# eMMC_SD.net
KiCad netlist of a schematic drawn in Altium Designer
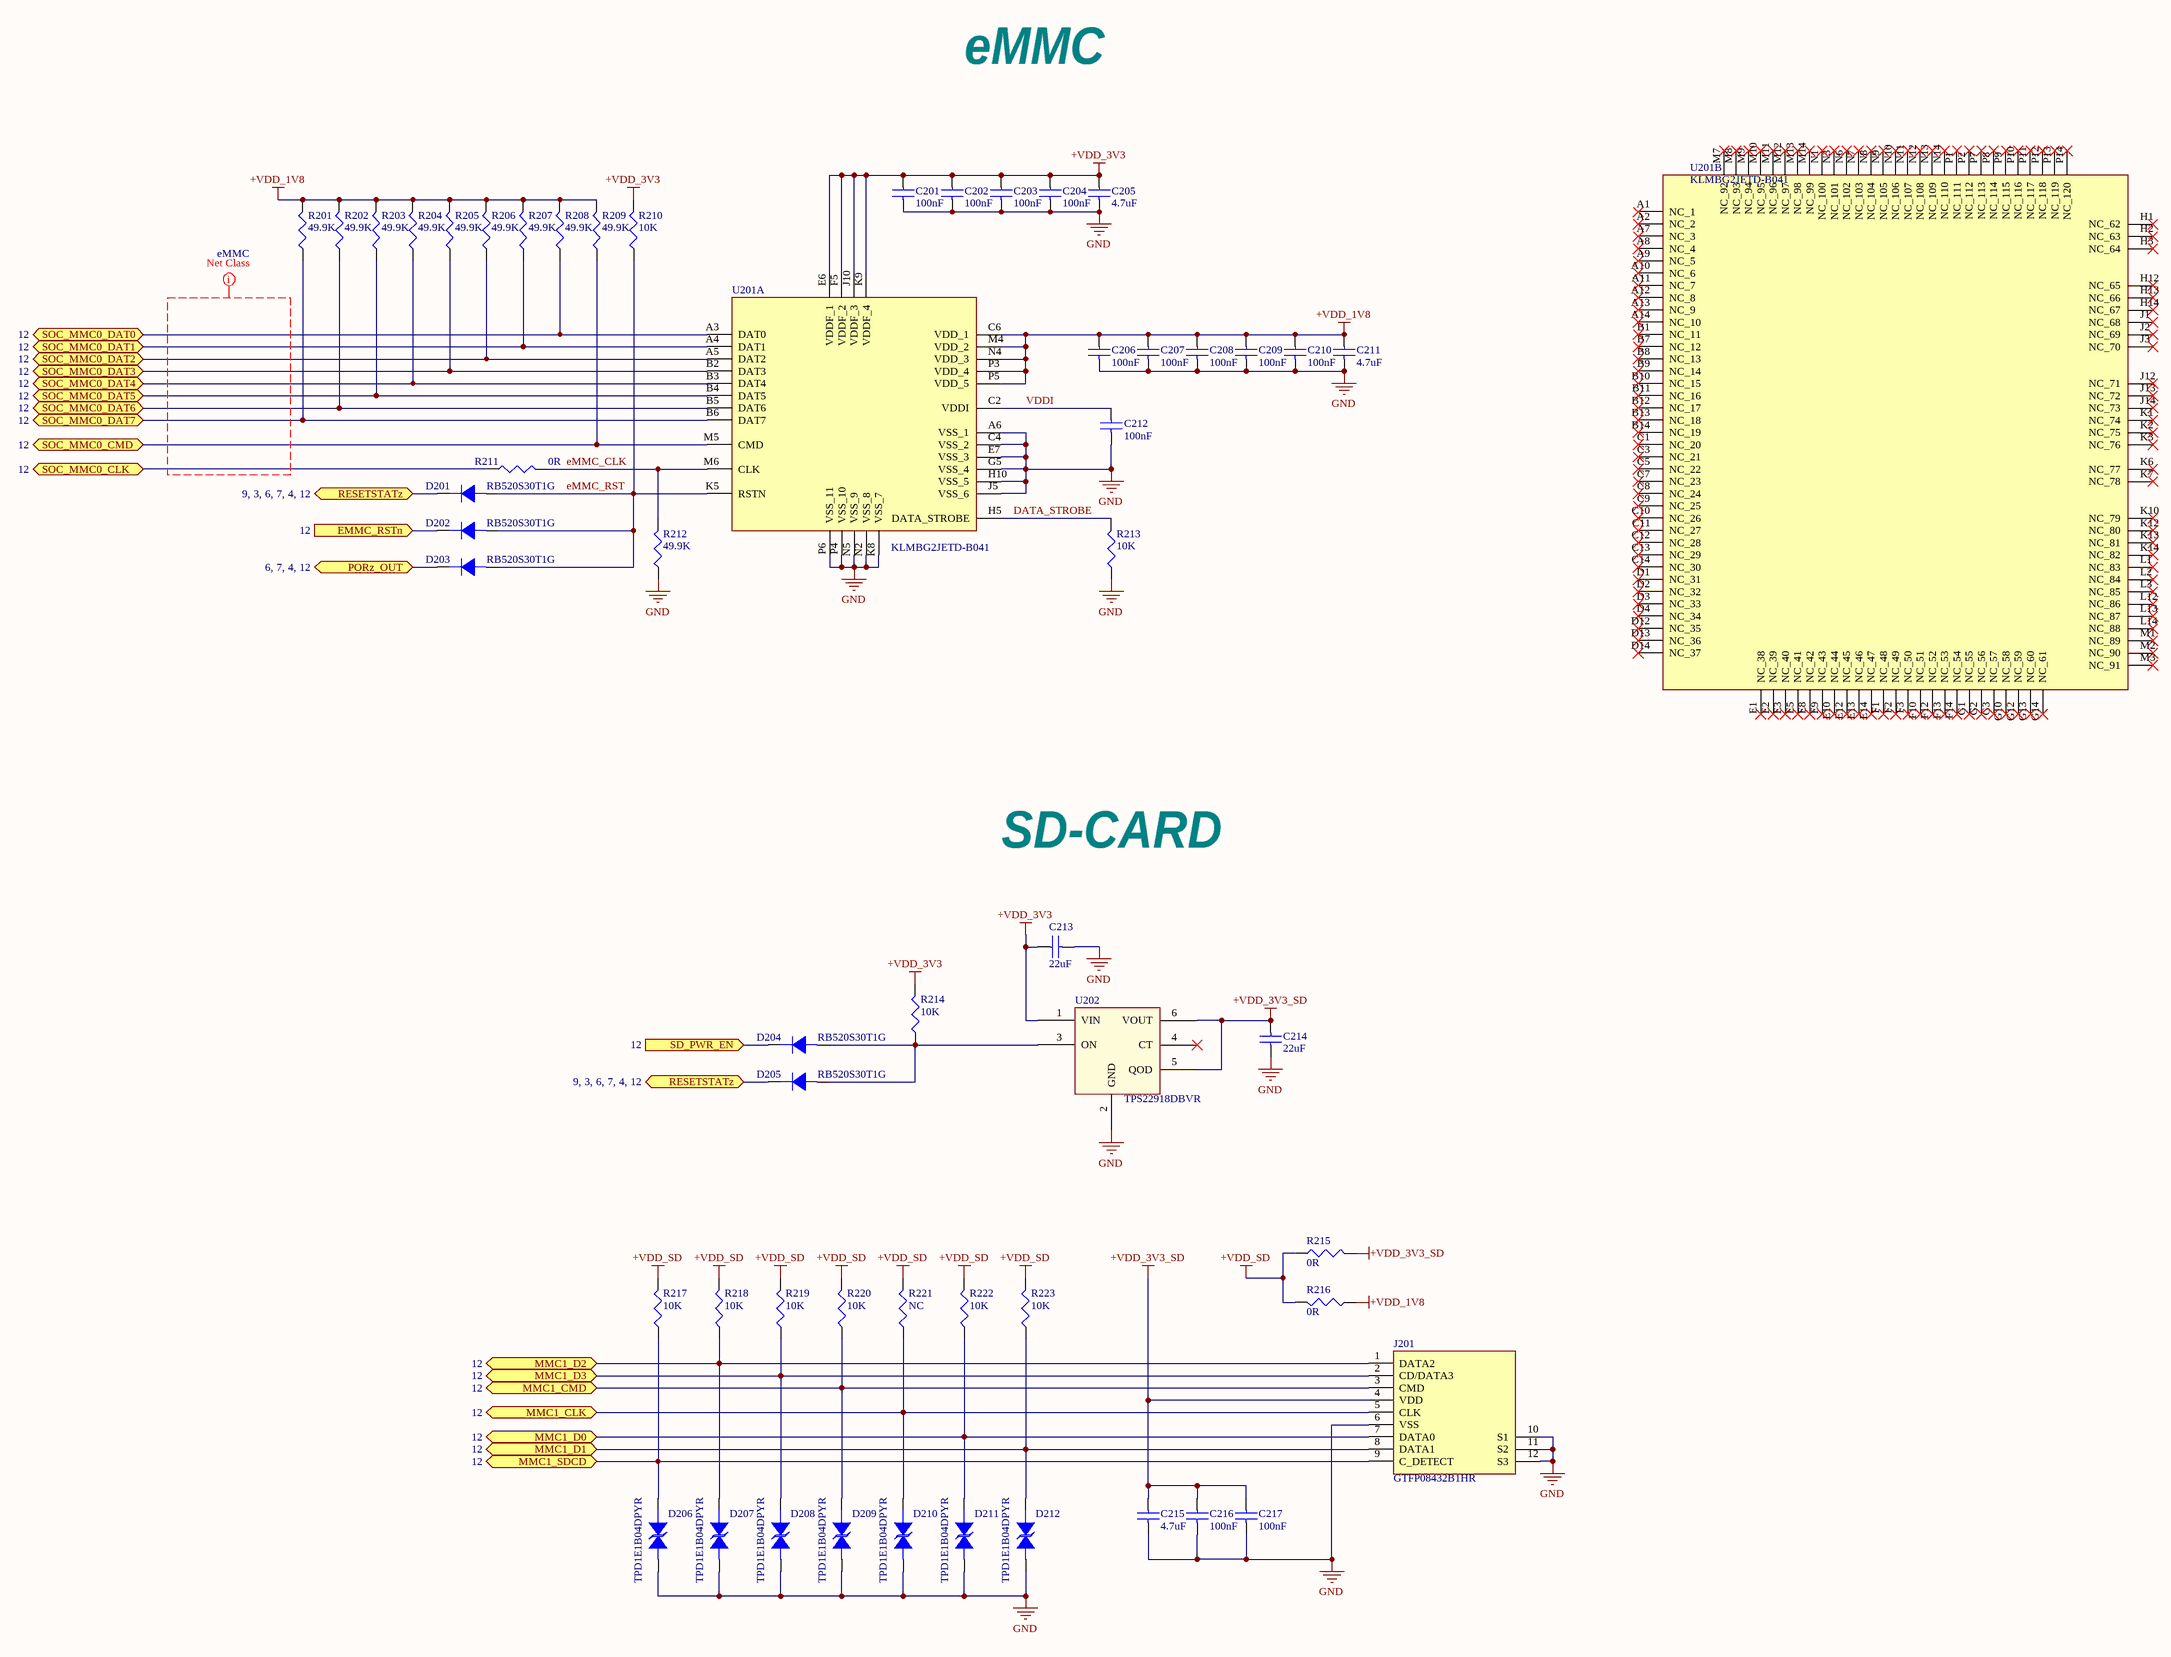
[diagram p0: eMMC&SD.SchDoc]

(export (version "E")
  (design (tool "Eeschema 10.0.6"))
  (components
    (comp (ref "C201")
      (value "100nF")
      (footprint "C0201")
      (description "Multilayer Ceramic Capacitor, 0.1 uF, 16 V, ± 10%, X5R, 0201 [0603 Metric]")
      (fields
        (field (name "MANUFACTURER") "Yageo")
        (field (name "MANUFACTURER PART NUMBER") "CC0201KRX5R6BB104")
      )
      (libsource (lib "Schlib SOM AM625") (part "CC0201KRX5R6BB104"))
    )
    (comp (ref "C202")
      (value "100nF")
      (footprint "C0201")
      (description "Multilayer Ceramic Capacitor, 0.1 uF, 16 V, ± 10%, X5R, 0201 [0603 Metric]")
      (fields
        (field (name "MANUFACTURER") "Yageo")
        (field (name "MANUFACTURER PART NUMBER") "CC0201KRX5R6BB104")
      )
      (libsource (lib "Schlib SOM AM625") (part "CC0201KRX5R6BB104"))
    )
    (comp (ref "C203")
      (value "100nF")
      (footprint "C0201")
      (description "Multilayer Ceramic Capacitor, 0.1 uF, 16 V, ± 10%, X5R, 0201 [0603 Metric]")
      (fields
        (field (name "MANUFACTURER") "Yageo")
        (field (name "MANUFACTURER PART NUMBER") "CC0201KRX5R6BB104")
      )
      (libsource (lib "Schlib SOM AM625") (part "CC0201KRX5R6BB104"))
    )
    (comp (ref "C204")
      (value "100nF")
      (footprint "C0201")
      (description "Multilayer Ceramic Capacitor, 0.1 uF, 16 V, ± 10%, X5R, 0201 [0603 Metric]")
      (fields
        (field (name "MANUFACTURER") "Yageo")
        (field (name "MANUFACTURER PART NUMBER") "CC0201KRX5R6BB104")
      )
      (libsource (lib "Schlib SOM AM625") (part "CC0201KRX5R6BB104"))
    )
    (comp (ref "C205")
      (value "4.7uF")
      (footprint "C0402")
      (description "Multilayer Ceramic Capacitor, 4.7 uF, 6.3V, ± 10%, X5R, 0402 [1005 Metric]")
      (fields
        (field (name "MANUFACTURER") "Yageo")
        (field (name "MANUFACTURER PART NUMBER") "CC0402MRX5R5BB475")
      )
      (libsource (lib "Schlib SOM AM625") (part "CC0402MRX5R5BB475"))
    )
    (comp (ref "C206")
      (value "100nF")
      (footprint "C0201")
      (description "Multilayer Ceramic Capacitor, 0.1 uF, 16 V, ± 10%, X5R, 0201 [0603 Metric]")
      (fields
        (field (name "MANUFACTURER") "Yageo")
        (field (name "MANUFACTURER PART NUMBER") "CC0201KRX5R6BB104")
      )
      (libsource (lib "Schlib SOM AM625") (part "CC0201KRX5R6BB104"))
    )
    (comp (ref "C207")
      (value "100nF")
      (footprint "C0201")
      (description "Multilayer Ceramic Capacitor, 0.1 uF, 16 V, ± 10%, X5R, 0201 [0603 Metric]")
      (fields
        (field (name "MANUFACTURER") "Yageo")
        (field (name "MANUFACTURER PART NUMBER") "CC0201KRX5R6BB104")
      )
      (libsource (lib "Schlib SOM AM625") (part "CC0201KRX5R6BB104"))
    )
    (comp (ref "C208")
      (value "100nF")
      (footprint "C0201")
      (description "Multilayer Ceramic Capacitor, 0.1 uF, 16 V, ± 10%, X5R, 0201 [0603 Metric]")
      (fields
        (field (name "MANUFACTURER") "Yageo")
        (field (name "MANUFACTURER PART NUMBER") "CC0201KRX5R6BB104")
      )
      (libsource (lib "Schlib SOM AM625") (part "CC0201KRX5R6BB104"))
    )
    (comp (ref "C209")
      (value "100nF")
      (footprint "C0201")
      (description "Multilayer Ceramic Capacitor, 0.1 uF, 16 V, ± 10%, X5R, 0201 [0603 Metric]")
      (fields
        (field (name "MANUFACTURER") "Yageo")
        (field (name "MANUFACTURER PART NUMBER") "CC0201KRX5R6BB104")
      )
      (libsource (lib "Schlib SOM AM625") (part "CC0201KRX5R6BB104"))
    )
    (comp (ref "C210")
      (value "100nF")
      (footprint "C0201")
      (description "Multilayer Ceramic Capacitor, 0.1 uF, 16 V, ± 10%, X5R, 0201 [0603 Metric]")
      (fields
        (field (name "MANUFACTURER") "Yageo")
        (field (name "MANUFACTURER PART NUMBER") "CC0201KRX5R6BB104")
      )
      (libsource (lib "Schlib SOM AM625") (part "CC0201KRX5R6BB104"))
    )
    (comp (ref "C211")
      (value "4.7uF")
      (footprint "C0402")
      (description "Multilayer Ceramic Capacitor, 4.7 uF, 6.3V, ± 10%, X5R, 0402 [1005 Metric]")
      (fields
        (field (name "MANUFACTURER") "Yageo")
        (field (name "MANUFACTURER PART NUMBER") "CC0402MRX5R5BB475")
      )
      (libsource (lib "Schlib SOM AM625") (part "CC0402MRX5R5BB475"))
    )
    (comp (ref "C212")
      (value "100nF")
      (footprint "C0201")
      (description "Multilayer Ceramic Capacitor, 0.1 uF, 16 V, ± 10%, X5R, 0201 [0603 Metric]")
      (fields
        (field (name "MANUFACTURER") "Yageo")
        (field (name "MANUFACTURER PART NUMBER") "CC0201KRX5R6BB104")
      )
      (libsource (lib "Schlib SOM AM625") (part "CC0201KRX5R6BB104"))
    )
    (comp (ref "C213")
      (value "22uF")
      (footprint "C0805")
      (description "22 µF ±20% 25V Ceramic Capacitor X5R 0805 (2012 Metric)")
      (fields
        (field (name "MANUFACTURER") "Yageo")
        (field (name "MANUFACTURER PART NUMBER") "CC0805MKX5R8BB226")
      )
      (libsource (lib "Schlib SOM AM625") (part "CC0805MKX5R8BB226"))
    )
    (comp (ref "C214")
      (value "22uF")
      (footprint "C0805")
      (description "22 µF ±20% 25V Ceramic Capacitor X5R 0805 (2012 Metric)")
      (fields
        (field (name "MANUFACTURER") "Yageo")
        (field (name "MANUFACTURER PART NUMBER") "CC0805MKX5R8BB226")
      )
      (libsource (lib "Schlib SOM AM625") (part "CC0805MKX5R8BB226"))
    )
    (comp (ref "C215")
      (value "4.7uF")
      (footprint "C0402")
      (description "Multilayer Ceramic Capacitor, 4.7 uF, 6.3V, ± 10%, X5R, 0402 [1005 Metric]")
      (fields
        (field (name "MANUFACTURER") "Yageo")
        (field (name "MANUFACTURER PART NUMBER") "CC0402MRX5R5BB475")
      )
      (libsource (lib "Schlib SOM AM625") (part "CC0402MRX5R5BB475"))
    )
    (comp (ref "C216")
      (value "100nF")
      (footprint "C0201")
      (description "Multilayer Ceramic Capacitor, 0.1 uF, 16 V, ± 10%, X5R, 0201 [0603 Metric]")
      (fields
        (field (name "MANUFACTURER") "Yageo")
        (field (name "MANUFACTURER PART NUMBER") "CC0201KRX5R6BB104")
      )
      (libsource (lib "Schlib SOM AM625") (part "CC0201KRX5R6BB104"))
    )
    (comp (ref "C217")
      (value "100nF")
      (footprint "C0201")
      (description "Multilayer Ceramic Capacitor, 0.1 uF, 16 V, ± 10%, X5R, 0201 [0603 Metric]")
      (fields
        (field (name "MANUFACTURER") "Yageo")
        (field (name "MANUFACTURER PART NUMBER") "CC0201KRX5R6BB104")
      )
      (libsource (lib "Schlib SOM AM625") (part "CC0201KRX5R6BB104"))
    )
    (comp (ref "D201")
      (value "RB520S30T1G")
      (footprint "sod_523")
      (description "Diode Schottky 30V 0.2A 2-Pin SOD-523 T/R - Product that comes on tape, but is not reeled")
      (fields (field (name "MANUFACTURER") "ON Semiconductor"))
      (libsource (lib "Schlib SOM AM625") (part "RB520S30T1G"))
    )
    (comp (ref "D202")
      (value "RB520S30T1G")
      (footprint "sod_523")
      (description "Diode Schottky 30V 0.2A 2-Pin SOD-523 T/R - Product that comes on tape, but is not reeled")
      (fields (field (name "MANUFACTURER") "ON Semiconductor"))
      (libsource (lib "Schlib SOM AM625") (part "RB520S30T1G"))
    )
    (comp (ref "D203")
      (value "RB520S30T1G")
      (footprint "sod_523")
      (description "Diode Schottky 30V 0.2A 2-Pin SOD-523 T/R - Product that comes on tape, but is not reeled")
      (fields (field (name "MANUFACTURER") "ON Semiconductor"))
      (libsource (lib "Schlib SOM AM625") (part "RB520S30T1G"))
    )
    (comp (ref "D204")
      (value "RB520S30T1G")
      (footprint "sod_523")
      (description "Diode Schottky 30V 0.2A 2-Pin SOD-523 T/R - Product that comes on tape, but is not reeled")
      (fields (field (name "MANUFACTURER") "ON Semiconductor"))
      (libsource (lib "Schlib SOM AM625") (part "RB520S30T1G"))
    )
    (comp (ref "D205")
      (value "RB520S30T1G")
      (footprint "sod_523")
      (description "Diode Schottky 30V 0.2A 2-Pin SOD-523 T/R - Product that comes on tape, but is not reeled")
      (fields (field (name "MANUFACTURER") "ON Semiconductor"))
      (libsource (lib "Schlib SOM AM625") (part "RB520S30T1G"))
    )
    (comp (ref "D206")
      (value "TPD1E1B04DPYR")
      (footprint "DIO_TPD1E05U06DPYR")
      (description "1-pF, ±3.6-V, ±30-kV ESD protection diode with 6-A 8/20-uS surge & Low Clamping in 0402 package")
      (fields (field (name "MANUFACTURER") "Texas Instruments"))
      (libsource (lib "Schlib SOM AM625") (part "TPD1E1B04DPYR"))
    )
    (comp (ref "D207")
      (value "TPD1E1B04DPYR")
      (footprint "DIO_TPD1E05U06DPYR")
      (description "1-pF, ±3.6-V, ±30-kV ESD protection diode with 6-A 8/20-uS surge & Low Clamping in 0402 package")
      (fields (field (name "MANUFACTURER") "Texas Instruments"))
      (libsource (lib "Schlib SOM AM625") (part "TPD1E1B04DPYR"))
    )
    (comp (ref "D208")
      (value "TPD1E1B04DPYR")
      (footprint "DIO_TPD1E05U06DPYR")
      (description "1-pF, ±3.6-V, ±30-kV ESD protection diode with 6-A 8/20-uS surge & Low Clamping in 0402 package")
      (fields (field (name "MANUFACTURER") "Texas Instruments"))
      (libsource (lib "Schlib SOM AM625") (part "TPD1E1B04DPYR"))
    )
    (comp (ref "D209")
      (value "TPD1E1B04DPYR")
      (footprint "DIO_TPD1E05U06DPYR")
      (description "1-pF, ±3.6-V, ±30-kV ESD protection diode with 6-A 8/20-uS surge & Low Clamping in 0402 package")
      (fields (field (name "MANUFACTURER") "Texas Instruments"))
      (libsource (lib "Schlib SOM AM625") (part "TPD1E1B04DPYR"))
    )
    (comp (ref "D210")
      (value "TPD1E1B04DPYR")
      (footprint "DIO_TPD1E05U06DPYR")
      (description "1-pF, ±3.6-V, ±30-kV ESD protection diode with 6-A 8/20-uS surge & Low Clamping in 0402 package")
      (fields (field (name "MANUFACTURER") "Texas Instruments"))
      (libsource (lib "Schlib SOM AM625") (part "TPD1E1B04DPYR"))
    )
    (comp (ref "D211")
      (value "TPD1E1B04DPYR")
      (footprint "DIO_TPD1E05U06DPYR")
      (description "1-pF, ±3.6-V, ±30-kV ESD protection diode with 6-A 8/20-uS surge & Low Clamping in 0402 package")
      (fields (field (name "MANUFACTURER") "Texas Instruments"))
      (libsource (lib "Schlib SOM AM625") (part "TPD1E1B04DPYR"))
    )
    (comp (ref "D212")
      (value "TPD1E1B04DPYR")
      (footprint "DIO_TPD1E05U06DPYR")
      (description "1-pF, ±3.6-V, ±30-kV ESD protection diode with 6-A 8/20-uS surge & Low Clamping in 0402 package")
      (fields (field (name "MANUFACTURER") "Texas Instruments"))
      (libsource (lib "Schlib SOM AM625") (part "TPD1E1B04DPYR"))
    )
    (comp (ref "J201")
      (value "GTFP08432B1HR")
      (footprint "AMPHENOL_GTFP08432B1HR")
      (description "MICRO SD PUSH/PUSH SMALL 8C")
      (libsource (lib "Schlib SOM AM625") (part "CONN; MICRO SD PUSH/PUSH SMALL 8C, 5033981892"))
    )
    (comp (ref "R201")
      (value "49.9K")
      (footprint "R0402")
      (description "SMD Chip Resistor, 49.9 kOhm, ± 1%, 63 mW, 0402 [1005 Metric], Thick Film, General Purpose")
      (fields
        (field (name "MANUFACTURER") "Yageo")
        (field (name "MANUFACTURER PART NUMBER") "RC0402FR-0749K9L")
      )
      (libsource (lib "Schlib SOM AM625") (part "RC0402FR-0749K9L"))
    )
    (comp (ref "R202")
      (value "49.9K")
      (footprint "R0402")
      (description "SMD Chip Resistor, 49.9 kOhm, ± 1%, 63 mW, 0402 [1005 Metric], Thick Film, General Purpose")
      (fields
        (field (name "MANUFACTURER") "Yageo")
        (field (name "MANUFACTURER PART NUMBER") "RC0402FR-0749K9L")
      )
      (libsource (lib "Schlib SOM AM625") (part "RC0402FR-0749K9L"))
    )
    (comp (ref "R203")
      (value "49.9K")
      (footprint "R0402")
      (description "SMD Chip Resistor, 49.9 kOhm, ± 1%, 63 mW, 0402 [1005 Metric], Thick Film, General Purpose")
      (fields
        (field (name "MANUFACTURER") "Yageo")
        (field (name "MANUFACTURER PART NUMBER") "RC0402FR-0749K9L")
      )
      (libsource (lib "Schlib SOM AM625") (part "RC0402FR-0749K9L"))
    )
    (comp (ref "R204")
      (value "49.9K")
      (footprint "R0402")
      (description "SMD Chip Resistor, 49.9 kOhm, ± 1%, 63 mW, 0402 [1005 Metric], Thick Film, General Purpose")
      (fields
        (field (name "MANUFACTURER") "Yageo")
        (field (name "MANUFACTURER PART NUMBER") "RC0402FR-0749K9L")
      )
      (libsource (lib "Schlib SOM AM625") (part "RC0402FR-0749K9L"))
    )
    (comp (ref "R205")
      (value "49.9K")
      (footprint "R0402")
      (description "SMD Chip Resistor, 49.9 kOhm, ± 1%, 63 mW, 0402 [1005 Metric], Thick Film, General Purpose")
      (fields
        (field (name "MANUFACTURER") "Yageo")
        (field (name "MANUFACTURER PART NUMBER") "RC0402FR-0749K9L")
      )
      (libsource (lib "Schlib SOM AM625") (part "RC0402FR-0749K9L"))
    )
    (comp (ref "R206")
      (value "49.9K")
      (footprint "R0402")
      (description "SMD Chip Resistor, 49.9 kOhm, ± 1%, 63 mW, 0402 [1005 Metric], Thick Film, General Purpose")
      (fields
        (field (name "MANUFACTURER") "Yageo")
        (field (name "MANUFACTURER PART NUMBER") "RC0402FR-0749K9L")
      )
      (libsource (lib "Schlib SOM AM625") (part "RC0402FR-0749K9L"))
    )
    (comp (ref "R207")
      (value "49.9K")
      (footprint "R0402")
      (description "SMD Chip Resistor, 49.9 kOhm, ± 1%, 63 mW, 0402 [1005 Metric], Thick Film, General Purpose")
      (fields
        (field (name "MANUFACTURER") "Yageo")
        (field (name "MANUFACTURER PART NUMBER") "RC0402FR-0749K9L")
      )
      (libsource (lib "Schlib SOM AM625") (part "RC0402FR-0749K9L"))
    )
    (comp (ref "R208")
      (value "49.9K")
      (footprint "R0402")
      (description "SMD Chip Resistor, 49.9 kOhm, ± 1%, 63 mW, 0402 [1005 Metric], Thick Film, General Purpose")
      (fields
        (field (name "MANUFACTURER") "Yageo")
        (field (name "MANUFACTURER PART NUMBER") "RC0402FR-0749K9L")
      )
      (libsource (lib "Schlib SOM AM625") (part "RC0402FR-0749K9L"))
    )
    (comp (ref "R209")
      (value "49.9K")
      (footprint "R0402")
      (description "SMD Chip Resistor, 49.9 kOhm, ± 1%, 63 mW, 0402 [1005 Metric], Thick Film, General Purpose")
      (fields
        (field (name "MANUFACTURER") "Yageo")
        (field (name "MANUFACTURER PART NUMBER") "RC0402FR-0749K9L")
      )
      (libsource (lib "Schlib SOM AM625") (part "RC0402FR-0749K9L"))
    )
    (comp (ref "R210")
      (value "10K")
      (footprint "R0402")
      (description "RES 10.0K OHM 1/16W 1% 0402 SMD")
      (fields
        (field (name "MANUFACTURER") "Yageo")
        (field (name "MANUFACTURER PART NUMBER") "RC0402FR-0710KL")
      )
      (libsource (lib "Schlib SOM AM625") (part "RC0402FR-0710KL"))
    )
    (comp (ref "R211")
      (value "0R")
      (footprint "R0402")
      (description "Zero Ohm Resistor, Jumper, 0402 [1005 Metric], Thick Film, 63 mW, 1 A, Surface Mount")
      (fields
        (field (name "MANUFACTURER") "Yageo")
        (field (name "MANUFACTURER PART NUMBER") "RC0402JR-070RL")
      )
      (libsource (lib "Schlib SOM AM625") (part "RC0402JR-070RL"))
    )
    (comp (ref "R212")
      (value "49.9K")
      (footprint "R0402")
      (description "SMD Chip Resistor, 49.9 kOhm, ± 1%, 63 mW, 0402 [1005 Metric], Thick Film, General Purpose")
      (fields
        (field (name "MANUFACTURER") "Yageo")
        (field (name "MANUFACTURER PART NUMBER") "RC0402FR-0749K9L")
      )
      (libsource (lib "Schlib SOM AM625") (part "RC0402FR-0749K9L"))
    )
    (comp (ref "R213")
      (value "10K")
      (footprint "R0402")
      (description "RES 10.0K OHM 1/16W 1% 0402 SMD")
      (fields
        (field (name "MANUFACTURER") "Yageo")
        (field (name "MANUFACTURER PART NUMBER") "RC0402FR-0710KL")
      )
      (libsource (lib "Schlib SOM AM625") (part "RC0402FR-0710KL"))
    )
    (comp (ref "R214")
      (value "10K")
      (footprint "R0402")
      (description "RES 10.0K OHM 1/16W 1% 0402 SMD")
      (fields
        (field (name "MANUFACTURER") "Yageo")
        (field (name "MANUFACTURER PART NUMBER") "RC0402FR-0710KL")
      )
      (libsource (lib "Schlib SOM AM625") (part "RC0402FR-0710KL"))
    )
    (comp (ref "R215")
      (value "0R")
      (footprint "R0402")
      (description "Zero Ohm Resistor, Jumper, 0402 [1005 Metric], Thick Film, 63 mW, 1 A, Surface Mount")
      (fields
        (field (name "MANUFACTURER") "Yageo")
        (field (name "MANUFACTURER PART NUMBER") "RC0402JR-070RL")
      )
      (libsource (lib "Schlib SOM AM625") (part "RC0402JR-070RL"))
    )
    (comp (ref "R216")
      (value "0R")
      (footprint "R0402")
      (description "Zero Ohm Resistor, Jumper, 0402 [1005 Metric], Thick Film, 63 mW, 1 A, Surface Mount")
      (fields
        (field (name "MANUFACTURER") "Yageo")
        (field (name "MANUFACTURER PART NUMBER") "RC0402JR-070RL")
      )
      (libsource (lib "Schlib SOM AM625") (part "RC0402JR-070RL"))
    )
    (comp (ref "R217")
      (value "10K")
      (footprint "R0402")
      (description "RES 10.0K OHM 1/16W 1% 0402 SMD")
      (fields
        (field (name "MANUFACTURER") "Yageo")
        (field (name "MANUFACTURER PART NUMBER") "RC0402FR-0710KL")
      )
      (libsource (lib "Schlib SOM AM625") (part "RC0402FR-0710KL"))
    )
    (comp (ref "R218")
      (value "10K")
      (footprint "R0402")
      (description "RES 10.0K OHM 1/16W 1% 0402 SMD")
      (fields
        (field (name "MANUFACTURER") "Yageo")
        (field (name "MANUFACTURER PART NUMBER") "RC0402FR-0710KL")
      )
      (libsource (lib "Schlib SOM AM625") (part "RC0402FR-0710KL"))
    )
    (comp (ref "R219")
      (value "10K")
      (footprint "R0402")
      (description "RES 10.0K OHM 1/16W 1% 0402 SMD")
      (fields
        (field (name "MANUFACTURER") "Yageo")
        (field (name "MANUFACTURER PART NUMBER") "RC0402FR-0710KL")
      )
      (libsource (lib "Schlib SOM AM625") (part "RC0402FR-0710KL"))
    )
    (comp (ref "R220")
      (value "10K")
      (footprint "R0402")
      (description "RES 10.0K OHM 1/16W 1% 0402 SMD")
      (fields
        (field (name "MANUFACTURER") "Yageo")
        (field (name "MANUFACTURER PART NUMBER") "RC0402FR-0710KL")
      )
      (libsource (lib "Schlib SOM AM625") (part "RC0402FR-0710KL"))
    )
    (comp (ref "R221")
      (value "NC")
      (footprint "R0402")
      (description "RES 10.0K OHM 1/16W 1% 0402 SMD")
      (fields
        (field (name "MANUFACTURER") "Yageo")
        (field (name "MANUFACTURER PART NUMBER") "RC0402FR-0710KL")
      )
      (libsource (lib "Schlib SOM AM625") (part "RC0402FR-0710KL"))
    )
    (comp (ref "R222")
      (value "10K")
      (footprint "R0402")
      (description "RES 10.0K OHM 1/16W 1% 0402 SMD")
      (fields
        (field (name "MANUFACTURER") "Yageo")
        (field (name "MANUFACTURER PART NUMBER") "RC0402FR-0710KL")
      )
      (libsource (lib "Schlib SOM AM625") (part "RC0402FR-0710KL"))
    )
    (comp (ref "R223")
      (value "10K")
      (footprint "R0402")
      (description "RES 10.0K OHM 1/16W 1% 0402 SMD")
      (fields
        (field (name "MANUFACTURER") "Yageo")
        (field (name "MANUFACTURER PART NUMBER") "RC0402FR-0710KL")
      )
      (libsource (lib "Schlib SOM AM625") (part "RC0402FR-0710KL"))
    )
    (comp (ref "U201")
      (value "KLMBG2JETD-B041")
      (footprint "BGA153C50P14X14_1150X1300X80")
      (description "eMMC 5.1 BGA-153 eMMC ROHS")
      (libsource (lib "Schlib1") (part "KLMAG1JETD-B041"))
    )
    (comp (ref "U202")
      (value "TPS22918DBVR")
      (footprint "SOT23-6")
      (description "IC SINGLE CHANNEL LOAD SWITCH")
      (fields (field (name "MANUFACTURER") "Texas Instruments"))
      (libsource (lib "Schlib SOM AM625") (part "TPS22918DBVR"))
    )
  )
  (nets
    (net (code "1") (name "+VDD_1V8") (class "Default")
      (node (ref "C206") (pin "1") (pinfunction "1_1") (pintype "passive"))
      (node (ref "C207") (pin "1") (pinfunction "1_1") (pintype "passive"))
      (node (ref "C208") (pin "1") (pinfunction "1_1") (pintype "passive"))
      (node (ref "C209") (pin "1") (pinfunction "1_1") (pintype "passive"))
      (node (ref "C210") (pin "1") (pinfunction "1_1") (pintype "passive"))
      (node (ref "C211") (pin "1") (pinfunction "1_1") (pintype "passive"))
      (node (ref "R201") (pin "2") (pinfunction "2_2") (pintype "passive"))
      (node (ref "R202") (pin "2") (pinfunction "2_2") (pintype "passive"))
      (node (ref "R203") (pin "2") (pinfunction "2_2") (pintype "passive"))
      (node (ref "R204") (pin "2") (pinfunction "2_2") (pintype "passive"))
      (node (ref "R205") (pin "2") (pinfunction "2_2") (pintype "passive"))
      (node (ref "R206") (pin "2") (pinfunction "2_2") (pintype "passive"))
      (node (ref "R207") (pin "2") (pinfunction "2_2") (pintype "passive"))
      (node (ref "R208") (pin "2") (pinfunction "2_2") (pintype "passive"))
      (node (ref "R209") (pin "2") (pinfunction "2_2") (pintype "passive"))
      (node (ref "R216") (pin "1") (pinfunction "1_1") (pintype "passive"))
      (node (ref "U201") (pin "C6") (pinfunction "VDD_1_C6") (pintype "passive"))
      (node (ref "U201") (pin "M4") (pinfunction "VDD_2_M4") (pintype "passive"))
      (node (ref "U201") (pin "N4") (pinfunction "VDD_3_N4") (pintype "passive"))
      (node (ref "U201") (pin "P3") (pinfunction "VDD_4_P3") (pintype "passive"))
      (node (ref "U201") (pin "P5") (pinfunction "VDD_5_P5") (pintype "passive"))
    )
    (net (code "2") (name "+VDD_3V3") (class "Default")
      (node (ref "C201") (pin "1") (pinfunction "1_1") (pintype "passive"))
      (node (ref "C202") (pin "1") (pinfunction "1_1") (pintype "passive"))
      (node (ref "C203") (pin "1") (pinfunction "1_1") (pintype "passive"))
      (node (ref "C204") (pin "1") (pinfunction "1_1") (pintype "passive"))
      (node (ref "C205") (pin "1") (pinfunction "1_1") (pintype "passive"))
      (node (ref "C213") (pin "1") (pinfunction "1_1") (pintype "passive"))
      (node (ref "R210") (pin "2") (pinfunction "2_2") (pintype "passive"))
      (node (ref "R214") (pin "2") (pinfunction "2_2") (pintype "passive"))
      (node (ref "U201") (pin "E6") (pinfunction "VDDF_1_E6") (pintype "passive"))
      (node (ref "U201") (pin "F5") (pinfunction "VDDF_2_F5") (pintype "passive"))
      (node (ref "U201") (pin "J10") (pinfunction "VDDF_3_J10") (pintype "passive"))
      (node (ref "U201") (pin "K9") (pinfunction "VDDF_4_K9") (pintype "passive"))
      (node (ref "U202") (pin "1") (pinfunction "VIN_1") (pintype "passive"))
    )
    (net (code "3") (name "+VDD_3V3_SD") (class "Default")
      (node (ref "C214") (pin "2") (pinfunction "2_2") (pintype "passive"))
      (node (ref "C215") (pin "1") (pinfunction "1_1") (pintype "passive"))
      (node (ref "C216") (pin "1") (pinfunction "1_1") (pintype "passive"))
      (node (ref "C217") (pin "1") (pinfunction "1_1") (pintype "passive"))
      (node (ref "J201") (pin "4") (pinfunction "VDD_4") (pintype "passive"))
      (node (ref "R215") (pin "2") (pinfunction "2_2") (pintype "passive"))
      (node (ref "U202") (pin "5") (pinfunction "QOD_5") (pintype "passive"))
      (node (ref "U202") (pin "6") (pinfunction "VOUT_6") (pintype "passive"))
    )
    (net (code "4") (name "+VDD_SD") (class "Default")
      (node (ref "R215") (pin "1") (pinfunction "1_1") (pintype "passive"))
      (node (ref "R216") (pin "2") (pinfunction "2_2") (pintype "passive"))
      (node (ref "R217") (pin "2") (pinfunction "2_2") (pintype "passive"))
      (node (ref "R218") (pin "2") (pinfunction "2_2") (pintype "passive"))
      (node (ref "R219") (pin "2") (pinfunction "2_2") (pintype "passive"))
      (node (ref "R220") (pin "2") (pinfunction "2_2") (pintype "passive"))
      (node (ref "R221") (pin "2") (pinfunction "2_2") (pintype "passive"))
      (node (ref "R222") (pin "2") (pinfunction "2_2") (pintype "passive"))
      (node (ref "R223") (pin "2") (pinfunction "2_2") (pintype "passive"))
    )
    (net (code "5") (name "/DATA_STROBE") (class "Default")
      (node (ref "R213") (pin "2") (pinfunction "2_2") (pintype "passive"))
      (node (ref "U201") (pin "H5") (pinfunction "DATA_STROBE_H5") (pintype "passive"))
    )
    (net (code "6") (name "/EMMC_RSTn") (class "Default")
      (node (ref "D202") (pin "2") (pinfunction "C_2") (pintype "passive"))
    )
    (net (code "7") (name "/MMC1_CLK") (class "Default")
      (node (ref "D210") (pin "2") (pinfunction "2_2") (pintype "passive"))
      (node (ref "J201") (pin "5") (pinfunction "CLK_5") (pintype "passive"))
      (node (ref "R221") (pin "1") (pinfunction "1_1") (pintype "passive"))
    )
    (net (code "8") (name "/MMC1_CMD") (class "Default")
      (node (ref "D209") (pin "2") (pinfunction "2_2") (pintype "passive"))
      (node (ref "J201") (pin "3") (pinfunction "CMD_3") (pintype "passive"))
      (node (ref "R220") (pin "1") (pinfunction "1_1") (pintype "passive"))
    )
    (net (code "9") (name "/MMC1_D0") (class "Default")
      (node (ref "D211") (pin "2") (pinfunction "2_2") (pintype "passive"))
      (node (ref "J201") (pin "7") (pinfunction "DATA0_7") (pintype "passive"))
      (node (ref "R222") (pin "1") (pinfunction "1_1") (pintype "passive"))
    )
    (net (code "10") (name "/MMC1_D1") (class "Default")
      (node (ref "D212") (pin "2") (pinfunction "2_2") (pintype "passive"))
      (node (ref "J201") (pin "8") (pinfunction "DATA1_8") (pintype "passive"))
      (node (ref "R223") (pin "1") (pinfunction "1_1") (pintype "passive"))
    )
    (net (code "11") (name "/MMC1_D2") (class "Default")
      (node (ref "D207") (pin "2") (pinfunction "2_2") (pintype "passive"))
      (node (ref "J201") (pin "1") (pinfunction "DATA2_1") (pintype "passive"))
      (node (ref "R218") (pin "1") (pinfunction "1_1") (pintype "passive"))
    )
    (net (code "12") (name "/MMC1_D3") (class "Default")
      (node (ref "D208") (pin "2") (pinfunction "2_2") (pintype "passive"))
      (node (ref "J201") (pin "2") (pinfunction "CD/DATA3_2") (pintype "passive"))
      (node (ref "R219") (pin "1") (pinfunction "1_1") (pintype "passive"))
    )
    (net (code "13") (name "/MMC1_SDCD") (class "Default")
      (node (ref "D206") (pin "2") (pinfunction "2_2") (pintype "passive"))
      (node (ref "J201") (pin "9") (pinfunction "C_DETECT_9") (pintype "passive"))
      (node (ref "R217") (pin "1") (pinfunction "1_1") (pintype "passive"))
    )
    (net (code "14") (name "/PORz_OUT") (class "Default")
      (node (ref "D203") (pin "2") (pinfunction "C_2") (pintype "passive"))
    )
    (net (code "15") (name "/RESETSTATz") (class "Default")
      (node (ref "D201") (pin "2") (pinfunction "C_2") (pintype "passive"))
      (node (ref "D205") (pin "2") (pinfunction "C_2") (pintype "passive"))
    )
    (net (code "16") (name "/SD_PWR_EN") (class "Default")
      (node (ref "D204") (pin "2") (pinfunction "C_2") (pintype "passive"))
    )
    (net (code "17") (name "/SOC_MMC0_CLK") (class "Default")
      (node (ref "R211") (pin "1") (pinfunction "1_1") (pintype "passive"))
    )
    (net (code "18") (name "/SOC_MMC0_CMD") (class "Default")
      (node (ref "R209") (pin "1") (pinfunction "1_1") (pintype "passive"))
      (node (ref "U201") (pin "M5") (pinfunction "CMD_M5") (pintype "passive"))
    )
    (net (code "19") (name "/SOC_MMC0_DAT0") (class "Default")
      (node (ref "R208") (pin "1") (pinfunction "1_1") (pintype "passive"))
      (node (ref "U201") (pin "A3") (pinfunction "DAT0_A3") (pintype "passive"))
    )
    (net (code "20") (name "/SOC_MMC0_DAT1") (class "Default")
      (node (ref "R207") (pin "1") (pinfunction "1_1") (pintype "passive"))
      (node (ref "U201") (pin "A4") (pinfunction "DAT1_A4") (pintype "passive"))
    )
    (net (code "21") (name "/SOC_MMC0_DAT2") (class "Default")
      (node (ref "R206") (pin "1") (pinfunction "1_1") (pintype "passive"))
      (node (ref "U201") (pin "A5") (pinfunction "DAT2_A5") (pintype "passive"))
    )
    (net (code "22") (name "/SOC_MMC0_DAT3") (class "Default")
      (node (ref "R205") (pin "1") (pinfunction "1_1") (pintype "passive"))
      (node (ref "U201") (pin "B2") (pinfunction "DAT3_B2") (pintype "passive"))
    )
    (net (code "23") (name "/SOC_MMC0_DAT4") (class "Default")
      (node (ref "R204") (pin "1") (pinfunction "1_1") (pintype "passive"))
      (node (ref "U201") (pin "B3") (pinfunction "DAT4_B3") (pintype "passive"))
    )
    (net (code "24") (name "/SOC_MMC0_DAT5") (class "Default")
      (node (ref "R203") (pin "1") (pinfunction "1_1") (pintype "passive"))
      (node (ref "U201") (pin "B4") (pinfunction "DAT5_B4") (pintype "passive"))
    )
    (net (code "25") (name "/SOC_MMC0_DAT6") (class "Default")
      (node (ref "R202") (pin "1") (pinfunction "1_1") (pintype "passive"))
      (node (ref "U201") (pin "B5") (pinfunction "DAT6_B5") (pintype "passive"))
    )
    (net (code "26") (name "/SOC_MMC0_DAT7") (class "Default")
      (node (ref "R201") (pin "1") (pinfunction "1_1") (pintype "passive"))
      (node (ref "U201") (pin "B6") (pinfunction "DAT7_B6") (pintype "passive"))
    )
    (net (code "27") (name "/VDDI") (class "Default")
      (node (ref "C212") (pin "1") (pinfunction "1_1") (pintype "passive"))
      (node (ref "U201") (pin "C2") (pinfunction "VDDI_C2") (pintype "passive"))
    )
    (net (code "28") (name "/eMMC_CLK") (class "Default")
      (node (ref "R211") (pin "2") (pinfunction "2_2") (pintype "passive"))
      (node (ref "R212") (pin "2") (pinfunction "2_2") (pintype "passive"))
      (node (ref "U201") (pin "M6") (pinfunction "CLK_M6") (pintype "passive"))
    )
    (net (code "29") (name "/eMMC_RST") (class "Default")
      (node (ref "D201") (pin "1") (pinfunction "A_1") (pintype "passive"))
      (node (ref "D202") (pin "1") (pinfunction "A_1") (pintype "passive"))
      (node (ref "D203") (pin "1") (pinfunction "A_1") (pintype "passive"))
      (node (ref "R210") (pin "1") (pinfunction "1_1") (pintype "passive"))
      (node (ref "U201") (pin "K5") (pinfunction "RSTN_K5") (pintype "passive"))
    )
    (net (code "30") (name "GND") (class "Default")
      (node (ref "C201") (pin "2") (pinfunction "2_2") (pintype "passive"))
      (node (ref "C202") (pin "2") (pinfunction "2_2") (pintype "passive"))
      (node (ref "C203") (pin "2") (pinfunction "2_2") (pintype "passive"))
      (node (ref "C204") (pin "2") (pinfunction "2_2") (pintype "passive"))
      (node (ref "C205") (pin "2") (pinfunction "2_2") (pintype "passive"))
      (node (ref "C206") (pin "2") (pinfunction "2_2") (pintype "passive"))
      (node (ref "C207") (pin "2") (pinfunction "2_2") (pintype "passive"))
      (node (ref "C208") (pin "2") (pinfunction "2_2") (pintype "passive"))
      (node (ref "C209") (pin "2") (pinfunction "2_2") (pintype "passive"))
      (node (ref "C210") (pin "2") (pinfunction "2_2") (pintype "passive"))
      (node (ref "C211") (pin "2") (pinfunction "2_2") (pintype "passive"))
      (node (ref "C212") (pin "2") (pinfunction "2_2") (pintype "passive"))
      (node (ref "C213") (pin "2") (pinfunction "2_2") (pintype "passive"))
      (node (ref "C214") (pin "1") (pinfunction "1_1") (pintype "passive"))
      (node (ref "C215") (pin "2") (pinfunction "2_2") (pintype "passive"))
      (node (ref "C216") (pin "2") (pinfunction "2_2") (pintype "passive"))
      (node (ref "C217") (pin "2") (pinfunction "2_2") (pintype "passive"))
      (node (ref "D206") (pin "1") (pinfunction "1_1") (pintype "passive"))
      (node (ref "D207") (pin "1") (pinfunction "1_1") (pintype "passive"))
      (node (ref "D208") (pin "1") (pinfunction "1_1") (pintype "passive"))
      (node (ref "D209") (pin "1") (pinfunction "1_1") (pintype "passive"))
      (node (ref "D210") (pin "1") (pinfunction "1_1") (pintype "passive"))
      (node (ref "D211") (pin "1") (pinfunction "1_1") (pintype "passive"))
      (node (ref "D212") (pin "1") (pinfunction "1_1") (pintype "passive"))
      (node (ref "J201") (pin "10") (pinfunction "S1_10") (pintype "passive"))
      (node (ref "J201") (pin "11") (pinfunction "S2_11") (pintype "passive"))
      (node (ref "J201") (pin "12") (pinfunction "S3_12") (pintype "passive"))
      (node (ref "J201") (pin "6") (pinfunction "VSS_6") (pintype "passive"))
      (node (ref "R212") (pin "1") (pinfunction "1_1") (pintype "passive"))
      (node (ref "R213") (pin "1") (pinfunction "1_1") (pintype "passive"))
      (node (ref "U201") (pin "A6") (pinfunction "VSS_1_A6") (pintype "passive"))
      (node (ref "U201") (pin "C4") (pinfunction "VSS_2_C4") (pintype "passive"))
      (node (ref "U201") (pin "E7") (pinfunction "VSS_3_E7") (pintype "passive"))
      (node (ref "U201") (pin "G5") (pinfunction "VSS_4_G5") (pintype "passive"))
      (node (ref "U201") (pin "H10") (pinfunction "VSS_5_H10") (pintype "passive"))
      (node (ref "U201") (pin "J5") (pinfunction "VSS_6_J5") (pintype "passive"))
      (node (ref "U201") (pin "K8") (pinfunction "VSS_7_K8") (pintype "passive"))
      (node (ref "U201") (pin "N2") (pinfunction "VSS_8_N2") (pintype "passive"))
      (node (ref "U201") (pin "N5") (pinfunction "VSS_9_N5") (pintype "passive"))
      (node (ref "U201") (pin "P4") (pinfunction "VSS_10_P4") (pintype "passive"))
      (node (ref "U201") (pin "P6") (pinfunction "VSS_11_P6") (pintype "passive"))
      (node (ref "U202") (pin "2") (pinfunction "GND_2") (pintype "power_in"))
    )
    (net (code "31") (name "Net-(D204-A)") (class "Default")
      (node (ref "D204") (pin "1") (pinfunction "A_1") (pintype "passive"))
      (node (ref "D205") (pin "1") (pinfunction "A_1") (pintype "passive"))
      (node (ref "R214") (pin "1") (pinfunction "1_1") (pintype "passive"))
      (node (ref "U202") (pin "3") (pinfunction "ON_3") (pintype "passive"))
    )
    (net (code "32") (name "unconnected-(U201B-NC_1-PadA1)") (class "Default")
      (node (ref "U201") (pin "A1") (pinfunction "NC_1_A1") (pintype "passive+no_connect"))
    )
    (net (code "33") (name "unconnected-(U201B-NC_2-PadA2)") (class "Default")
      (node (ref "U201") (pin "A2") (pinfunction "NC_2_A2") (pintype "passive+no_connect"))
    )
    (net (code "34") (name "unconnected-(U201B-NC_3-PadA7)") (class "Default")
      (node (ref "U201") (pin "A7") (pinfunction "NC_3_A7") (pintype "passive+no_connect"))
    )
    (net (code "35") (name "unconnected-(U201B-NC_4-PadA8)") (class "Default")
      (node (ref "U201") (pin "A8") (pinfunction "NC_4_A8") (pintype "passive+no_connect"))
    )
    (net (code "36") (name "unconnected-(U201B-NC_5-PadA9)") (class "Default")
      (node (ref "U201") (pin "A9") (pinfunction "NC_5_A9") (pintype "passive+no_connect"))
    )
    (net (code "37") (name "unconnected-(U201B-NC_6-PadA10)") (class "Default")
      (node (ref "U201") (pin "A10") (pinfunction "NC_6_A10") (pintype "passive+no_connect"))
    )
    (net (code "38") (name "unconnected-(U201B-NC_7-PadA11)") (class "Default")
      (node (ref "U201") (pin "A11") (pinfunction "NC_7_A11") (pintype "passive+no_connect"))
    )
    (net (code "39") (name "unconnected-(U201B-NC_8-PadA12)") (class "Default")
      (node (ref "U201") (pin "A12") (pinfunction "NC_8_A12") (pintype "passive+no_connect"))
    )
    (net (code "40") (name "unconnected-(U201B-NC_9-PadA13)") (class "Default")
      (node (ref "U201") (pin "A13") (pinfunction "NC_9_A13") (pintype "passive+no_connect"))
    )
    (net (code "41") (name "unconnected-(U201B-NC_10-PadA14)") (class "Default")
      (node (ref "U201") (pin "A14") (pinfunction "NC_10_A14") (pintype "passive+no_connect"))
    )
    (net (code "42") (name "unconnected-(U201B-NC_11-PadB1)") (class "Default")
      (node (ref "U201") (pin "B1") (pinfunction "NC_11_B1") (pintype "passive+no_connect"))
    )
    (net (code "43") (name "unconnected-(U201B-NC_12-PadB7)") (class "Default")
      (node (ref "U201") (pin "B7") (pinfunction "NC_12_B7") (pintype "passive+no_connect"))
    )
    (net (code "44") (name "unconnected-(U201B-NC_13-PadB8)") (class "Default")
      (node (ref "U201") (pin "B8") (pinfunction "NC_13_B8") (pintype "passive+no_connect"))
    )
    (net (code "45") (name "unconnected-(U201B-NC_14-PadB9)") (class "Default")
      (node (ref "U201") (pin "B9") (pinfunction "NC_14_B9") (pintype "passive+no_connect"))
    )
    (net (code "46") (name "unconnected-(U201B-NC_15-PadB10)") (class "Default")
      (node (ref "U201") (pin "B10") (pinfunction "NC_15_B10") (pintype "passive+no_connect"))
    )
    (net (code "47") (name "unconnected-(U201B-NC_16-PadB11)") (class "Default")
      (node (ref "U201") (pin "B11") (pinfunction "NC_16_B11") (pintype "passive+no_connect"))
    )
    (net (code "48") (name "unconnected-(U201B-NC_17-PadB12)") (class "Default")
      (node (ref "U201") (pin "B12") (pinfunction "NC_17_B12") (pintype "passive+no_connect"))
    )
    (net (code "49") (name "unconnected-(U201B-NC_18-PadB13)") (class "Default")
      (node (ref "U201") (pin "B13") (pinfunction "NC_18_B13") (pintype "passive+no_connect"))
    )
    (net (code "50") (name "unconnected-(U201B-NC_19-PadB14)") (class "Default")
      (node (ref "U201") (pin "B14") (pinfunction "NC_19_B14") (pintype "passive+no_connect"))
    )
    (net (code "51") (name "unconnected-(U201B-NC_20-PadC1)") (class "Default")
      (node (ref "U201") (pin "C1") (pinfunction "NC_20_C1") (pintype "passive+no_connect"))
    )
    (net (code "52") (name "unconnected-(U201B-NC_21-PadC3)") (class "Default")
      (node (ref "U201") (pin "C3") (pinfunction "NC_21_C3") (pintype "passive+no_connect"))
    )
    (net (code "53") (name "unconnected-(U201B-NC_22-PadC5)") (class "Default")
      (node (ref "U201") (pin "C5") (pinfunction "NC_22_C5") (pintype "passive+no_connect"))
    )
    (net (code "54") (name "unconnected-(U201B-NC_23-PadC7)") (class "Default")
      (node (ref "U201") (pin "C7") (pinfunction "NC_23_C7") (pintype "passive+no_connect"))
    )
    (net (code "55") (name "unconnected-(U201B-NC_24-PadC8)") (class "Default")
      (node (ref "U201") (pin "C8") (pinfunction "NC_24_C8") (pintype "passive+no_connect"))
    )
    (net (code "56") (name "unconnected-(U201B-NC_25-PadC9)") (class "Default")
      (node (ref "U201") (pin "C9") (pinfunction "NC_25_C9") (pintype "passive+no_connect"))
    )
    (net (code "57") (name "unconnected-(U201B-NC_26-PadC10)") (class "Default")
      (node (ref "U201") (pin "C10") (pinfunction "NC_26_C10") (pintype "passive+no_connect"))
    )
    (net (code "58") (name "unconnected-(U201B-NC_27-PadC11)") (class "Default")
      (node (ref "U201") (pin "C11") (pinfunction "NC_27_C11") (pintype "passive+no_connect"))
    )
    (net (code "59") (name "unconnected-(U201B-NC_28-PadC12)") (class "Default")
      (node (ref "U201") (pin "C12") (pinfunction "NC_28_C12") (pintype "passive+no_connect"))
    )
    (net (code "60") (name "unconnected-(U201B-NC_29-PadC13)") (class "Default")
      (node (ref "U201") (pin "C13") (pinfunction "NC_29_C13") (pintype "passive+no_connect"))
    )
    (net (code "61") (name "unconnected-(U201B-NC_30-PadC14)") (class "Default")
      (node (ref "U201") (pin "C14") (pinfunction "NC_30_C14") (pintype "passive+no_connect"))
    )
    (net (code "62") (name "unconnected-(U201B-NC_31-PadD1)") (class "Default")
      (node (ref "U201") (pin "D1") (pinfunction "NC_31_D1") (pintype "passive+no_connect"))
    )
    (net (code "63") (name "unconnected-(U201B-NC_32-PadD2)") (class "Default")
      (node (ref "U201") (pin "D2") (pinfunction "NC_32_D2") (pintype "passive+no_connect"))
    )
    (net (code "64") (name "unconnected-(U201B-NC_33-PadD3)") (class "Default")
      (node (ref "U201") (pin "D3") (pinfunction "NC_33_D3") (pintype "passive+no_connect"))
    )
    (net (code "65") (name "unconnected-(U201B-NC_34-PadD4)") (class "Default")
      (node (ref "U201") (pin "D4") (pinfunction "NC_34_D4") (pintype "passive+no_connect"))
    )
    (net (code "66") (name "unconnected-(U201B-NC_35-PadD12)") (class "Default")
      (node (ref "U201") (pin "D12") (pinfunction "NC_35_D12") (pintype "passive+no_connect"))
    )
    (net (code "67") (name "unconnected-(U201B-NC_36-PadD13)") (class "Default")
      (node (ref "U201") (pin "D13") (pinfunction "NC_36_D13") (pintype "passive+no_connect"))
    )
    (net (code "68") (name "unconnected-(U201B-NC_37-PadD14)") (class "Default")
      (node (ref "U201") (pin "D14") (pinfunction "NC_37_D14") (pintype "passive+no_connect"))
    )
    (net (code "69") (name "unconnected-(U201B-NC_38-PadE1)") (class "Default")
      (node (ref "U201") (pin "E1") (pinfunction "NC_38_E1") (pintype "passive+no_connect"))
    )
    (net (code "70") (name "unconnected-(U201B-NC_39-PadE2)") (class "Default")
      (node (ref "U201") (pin "E2") (pinfunction "NC_39_E2") (pintype "passive+no_connect"))
    )
    (net (code "71") (name "unconnected-(U201B-NC_40-PadE3)") (class "Default")
      (node (ref "U201") (pin "E3") (pinfunction "NC_40_E3") (pintype "passive+no_connect"))
    )
    (net (code "72") (name "unconnected-(U201B-NC_41-PadE5)") (class "Default")
      (node (ref "U201") (pin "E5") (pinfunction "NC_41_E5") (pintype "passive+no_connect"))
    )
    (net (code "73") (name "unconnected-(U201B-NC_42-PadE8)") (class "Default")
      (node (ref "U201") (pin "E8") (pinfunction "NC_42_E8") (pintype "passive+no_connect"))
    )
    (net (code "74") (name "unconnected-(U201B-NC_43-PadE9)") (class "Default")
      (node (ref "U201") (pin "E9") (pinfunction "NC_43_E9") (pintype "passive+no_connect"))
    )
    (net (code "75") (name "unconnected-(U201B-NC_44-PadE10)") (class "Default")
      (node (ref "U201") (pin "E10") (pinfunction "NC_44_E10") (pintype "passive+no_connect"))
    )
    (net (code "76") (name "unconnected-(U201B-NC_45-PadE12)") (class "Default")
      (node (ref "U201") (pin "E12") (pinfunction "NC_45_E12") (pintype "passive+no_connect"))
    )
    (net (code "77") (name "unconnected-(U201B-NC_46-PadE13)") (class "Default")
      (node (ref "U201") (pin "E13") (pinfunction "NC_46_E13") (pintype "passive+no_connect"))
    )
    (net (code "78") (name "unconnected-(U201B-NC_47-PadE14)") (class "Default")
      (node (ref "U201") (pin "E14") (pinfunction "NC_47_E14") (pintype "passive+no_connect"))
    )
    (net (code "79") (name "unconnected-(U201B-NC_48-PadF1)") (class "Default")
      (node (ref "U201") (pin "F1") (pinfunction "NC_48_F1") (pintype "passive+no_connect"))
    )
    (net (code "80") (name "unconnected-(U201B-NC_49-PadF2)") (class "Default")
      (node (ref "U201") (pin "F2") (pinfunction "NC_49_F2") (pintype "passive+no_connect"))
    )
    (net (code "81") (name "unconnected-(U201B-NC_50-PadF3)") (class "Default")
      (node (ref "U201") (pin "F3") (pinfunction "NC_50_F3") (pintype "passive+no_connect"))
    )
    (net (code "82") (name "unconnected-(U201B-NC_51-PadF10)") (class "Default")
      (node (ref "U201") (pin "F10") (pinfunction "NC_51_F10") (pintype "passive+no_connect"))
    )
    (net (code "83") (name "unconnected-(U201B-NC_52-PadF12)") (class "Default")
      (node (ref "U201") (pin "F12") (pinfunction "NC_52_F12") (pintype "passive+no_connect"))
    )
    (net (code "84") (name "unconnected-(U201B-NC_53-PadF13)") (class "Default")
      (node (ref "U201") (pin "F13") (pinfunction "NC_53_F13") (pintype "passive+no_connect"))
    )
    (net (code "85") (name "unconnected-(U201B-NC_54-PadF14)") (class "Default")
      (node (ref "U201") (pin "F14") (pinfunction "NC_54_F14") (pintype "passive+no_connect"))
    )
    (net (code "86") (name "unconnected-(U201B-NC_55-PadG1)") (class "Default")
      (node (ref "U201") (pin "G1") (pinfunction "NC_55_G1") (pintype "passive+no_connect"))
    )
    (net (code "87") (name "unconnected-(U201B-NC_56-PadG2)") (class "Default")
      (node (ref "U201") (pin "G2") (pinfunction "NC_56_G2") (pintype "passive+no_connect"))
    )
    (net (code "88") (name "unconnected-(U201B-NC_57-PadG3)") (class "Default")
      (node (ref "U201") (pin "G3") (pinfunction "NC_57_G3") (pintype "passive+no_connect"))
    )
    (net (code "89") (name "unconnected-(U201B-NC_58-PadG10)") (class "Default")
      (node (ref "U201") (pin "G10") (pinfunction "NC_58_G10") (pintype "passive+no_connect"))
    )
    (net (code "90") (name "unconnected-(U201B-NC_59-PadG12)") (class "Default")
      (node (ref "U201") (pin "G12") (pinfunction "NC_59_G12") (pintype "passive+no_connect"))
    )
    (net (code "91") (name "unconnected-(U201B-NC_60-PadG13)") (class "Default")
      (node (ref "U201") (pin "G13") (pinfunction "NC_60_G13") (pintype "passive+no_connect"))
    )
    (net (code "92") (name "unconnected-(U201B-NC_61-PadG14)") (class "Default")
      (node (ref "U201") (pin "G14") (pinfunction "NC_61_G14") (pintype "passive+no_connect"))
    )
    (net (code "93") (name "unconnected-(U201B-NC_62-PadH1)") (class "Default")
      (node (ref "U201") (pin "H1") (pinfunction "NC_62_H1") (pintype "passive+no_connect"))
    )
    (net (code "94") (name "unconnected-(U201B-NC_63-PadH2)") (class "Default")
      (node (ref "U201") (pin "H2") (pinfunction "NC_63_H2") (pintype "passive+no_connect"))
    )
    (net (code "95") (name "unconnected-(U201B-NC_64-PadH3)") (class "Default")
      (node (ref "U201") (pin "H3") (pinfunction "NC_64_H3") (pintype "passive+no_connect"))
    )
    (net (code "96") (name "unconnected-(U201B-NC_65-PadH12)") (class "Default")
      (node (ref "U201") (pin "H12") (pinfunction "NC_65_H12") (pintype "passive+no_connect"))
    )
    (net (code "97") (name "unconnected-(U201B-NC_66-PadH13)") (class "Default")
      (node (ref "U201") (pin "H13") (pinfunction "NC_66_H13") (pintype "passive+no_connect"))
    )
    (net (code "98") (name "unconnected-(U201B-NC_67-PadH14)") (class "Default")
      (node (ref "U201") (pin "H14") (pinfunction "NC_67_H14") (pintype "passive+no_connect"))
    )
    (net (code "99") (name "unconnected-(U201B-NC_68-PadJ1)") (class "Default")
      (node (ref "U201") (pin "J1") (pinfunction "NC_68_J1") (pintype "passive+no_connect"))
    )
    (net (code "100") (name "unconnected-(U201B-NC_69-PadJ2)") (class "Default")
      (node (ref "U201") (pin "J2") (pinfunction "NC_69_J2") (pintype "passive+no_connect"))
    )
    (net (code "101") (name "unconnected-(U201B-NC_70-PadJ3)") (class "Default")
      (node (ref "U201") (pin "J3") (pinfunction "NC_70_J3") (pintype "passive+no_connect"))
    )
    (net (code "102") (name "unconnected-(U201B-NC_71-PadJ12)") (class "Default")
      (node (ref "U201") (pin "J12") (pinfunction "NC_71_J12") (pintype "passive+no_connect"))
    )
    (net (code "103") (name "unconnected-(U201B-NC_72-PadJ13)") (class "Default")
      (node (ref "U201") (pin "J13") (pinfunction "NC_72_J13") (pintype "passive+no_connect"))
    )
    (net (code "104") (name "unconnected-(U201B-NC_73-PadJ14)") (class "Default")
      (node (ref "U201") (pin "J14") (pinfunction "NC_73_J14") (pintype "passive+no_connect"))
    )
    (net (code "105") (name "unconnected-(U201B-NC_74-PadK1)") (class "Default")
      (node (ref "U201") (pin "K1") (pinfunction "NC_74_K1") (pintype "passive+no_connect"))
    )
    (net (code "106") (name "unconnected-(U201B-NC_75-PadK2)") (class "Default")
      (node (ref "U201") (pin "K2") (pinfunction "NC_75_K2") (pintype "passive+no_connect"))
    )
    (net (code "107") (name "unconnected-(U201B-NC_76-PadK3)") (class "Default")
      (node (ref "U201") (pin "K3") (pinfunction "NC_76_K3") (pintype "passive+no_connect"))
    )
    (net (code "108") (name "unconnected-(U201B-NC_77-PadK6)") (class "Default")
      (node (ref "U201") (pin "K6") (pinfunction "NC_77_K6") (pintype "passive+no_connect"))
    )
    (net (code "109") (name "unconnected-(U201B-NC_78-PadK7)") (class "Default")
      (node (ref "U201") (pin "K7") (pinfunction "NC_78_K7") (pintype "passive+no_connect"))
    )
    (net (code "110") (name "unconnected-(U201B-NC_79-PadK10)") (class "Default")
      (node (ref "U201") (pin "K10") (pinfunction "NC_79_K10") (pintype "passive+no_connect"))
    )
    (net (code "111") (name "unconnected-(U201B-NC_80-PadK12)") (class "Default")
      (node (ref "U201") (pin "K12") (pinfunction "NC_80_K12") (pintype "passive+no_connect"))
    )
    (net (code "112") (name "unconnected-(U201B-NC_81-PadK13)") (class "Default")
      (node (ref "U201") (pin "K13") (pinfunction "NC_81_K13") (pintype "passive+no_connect"))
    )
    (net (code "113") (name "unconnected-(U201B-NC_82-PadK14)") (class "Default")
      (node (ref "U201") (pin "K14") (pinfunction "NC_82_K14") (pintype "passive+no_connect"))
    )
    (net (code "114") (name "unconnected-(U201B-NC_83-PadL1)") (class "Default")
      (node (ref "U201") (pin "L1") (pinfunction "NC_83_L1") (pintype "passive+no_connect"))
    )
    (net (code "115") (name "unconnected-(U201B-NC_84-PadL2)") (class "Default")
      (node (ref "U201") (pin "L2") (pinfunction "NC_84_L2") (pintype "passive+no_connect"))
    )
    (net (code "116") (name "unconnected-(U201B-NC_85-PadL3)") (class "Default")
      (node (ref "U201") (pin "L3") (pinfunction "NC_85_L3") (pintype "passive+no_connect"))
    )
    (net (code "117") (name "unconnected-(U201B-NC_86-PadL12)") (class "Default")
      (node (ref "U201") (pin "L12") (pinfunction "NC_86_L12") (pintype "passive+no_connect"))
    )
    (net (code "118") (name "unconnected-(U201B-NC_87-PadL13)") (class "Default")
      (node (ref "U201") (pin "L13") (pinfunction "NC_87_L13") (pintype "passive+no_connect"))
    )
    (net (code "119") (name "unconnected-(U201B-NC_88-PadL14)") (class "Default")
      (node (ref "U201") (pin "L14") (pinfunction "NC_88_L14") (pintype "passive+no_connect"))
    )
    (net (code "120") (name "unconnected-(U201B-NC_89-PadM1)") (class "Default")
      (node (ref "U201") (pin "M1") (pinfunction "NC_89_M1") (pintype "passive+no_connect"))
    )
    (net (code "121") (name "unconnected-(U201B-NC_90-PadM2)") (class "Default")
      (node (ref "U201") (pin "M2") (pinfunction "NC_90_M2") (pintype "passive+no_connect"))
    )
    (net (code "122") (name "unconnected-(U201B-NC_91-PadM3)") (class "Default")
      (node (ref "U201") (pin "M3") (pinfunction "NC_91_M3") (pintype "passive+no_connect"))
    )
    (net (code "123") (name "unconnected-(U201B-NC_92-PadM7)") (class "Default")
      (node (ref "U201") (pin "M7") (pinfunction "NC_92_M7") (pintype "passive+no_connect"))
    )
    (net (code "124") (name "unconnected-(U201B-NC_93-PadM8)") (class "Default")
      (node (ref "U201") (pin "M8") (pinfunction "NC_93_M8") (pintype "passive+no_connect"))
    )
    (net (code "125") (name "unconnected-(U201B-NC_94-PadM9)") (class "Default")
      (node (ref "U201") (pin "M9") (pinfunction "NC_94_M9") (pintype "passive+no_connect"))
    )
    (net (code "126") (name "unconnected-(U201B-NC_95-PadM10)") (class "Default")
      (node (ref "U201") (pin "M10") (pinfunction "NC_95_M10") (pintype "passive+no_connect"))
    )
    (net (code "127") (name "unconnected-(U201B-NC_96-PadM11)") (class "Default")
      (node (ref "U201") (pin "M11") (pinfunction "NC_96_M11") (pintype "passive+no_connect"))
    )
    (net (code "128") (name "unconnected-(U201B-NC_97-PadM12)") (class "Default")
      (node (ref "U201") (pin "M12") (pinfunction "NC_97_M12") (pintype "passive+no_connect"))
    )
    (net (code "129") (name "unconnected-(U201B-NC_98-PadM13)") (class "Default")
      (node (ref "U201") (pin "M13") (pinfunction "NC_98_M13") (pintype "passive+no_connect"))
    )
    (net (code "130") (name "unconnected-(U201B-NC_99-PadM14)") (class "Default")
      (node (ref "U201") (pin "M14") (pinfunction "NC_99_M14") (pintype "passive+no_connect"))
    )
    (net (code "131") (name "unconnected-(U201B-NC_100-PadN1)") (class "Default")
      (node (ref "U201") (pin "N1") (pinfunction "NC_100_N1") (pintype "passive+no_connect"))
    )
    (net (code "132") (name "unconnected-(U201B-NC_101-PadN3)") (class "Default")
      (node (ref "U201") (pin "N3") (pinfunction "NC_101_N3") (pintype "passive+no_connect"))
    )
    (net (code "133") (name "unconnected-(U201B-NC_102-PadN6)") (class "Default")
      (node (ref "U201") (pin "N6") (pinfunction "NC_102_N6") (pintype "passive+no_connect"))
    )
    (net (code "134") (name "unconnected-(U201B-NC_103-PadN7)") (class "Default")
      (node (ref "U201") (pin "N7") (pinfunction "NC_103_N7") (pintype "passive+no_connect"))
    )
    (net (code "135") (name "unconnected-(U201B-NC_104-PadN8)") (class "Default")
      (node (ref "U201") (pin "N8") (pinfunction "NC_104_N8") (pintype "passive+no_connect"))
    )
    (net (code "136") (name "unconnected-(U201B-NC_105-PadN9)") (class "Default")
      (node (ref "U201") (pin "N9") (pinfunction "NC_105_N9") (pintype "passive+no_connect"))
    )
    (net (code "137") (name "unconnected-(U201B-NC_106-PadN10)") (class "Default")
      (node (ref "U201") (pin "N10") (pinfunction "NC_106_N10") (pintype "passive+no_connect"))
    )
    (net (code "138") (name "unconnected-(U201B-NC_107-PadN11)") (class "Default")
      (node (ref "U201") (pin "N11") (pinfunction "NC_107_N11") (pintype "passive+no_connect"))
    )
    (net (code "139") (name "unconnected-(U201B-NC_108-PadN12)") (class "Default")
      (node (ref "U201") (pin "N12") (pinfunction "NC_108_N12") (pintype "passive+no_connect"))
    )
    (net (code "140") (name "unconnected-(U201B-NC_109-PadN13)") (class "Default")
      (node (ref "U201") (pin "N13") (pinfunction "NC_109_N13") (pintype "passive+no_connect"))
    )
    (net (code "141") (name "unconnected-(U201B-NC_110-PadN14)") (class "Default")
      (node (ref "U201") (pin "N14") (pinfunction "NC_110_N14") (pintype "passive+no_connect"))
    )
    (net (code "142") (name "unconnected-(U201B-NC_111-PadP1)") (class "Default")
      (node (ref "U201") (pin "P1") (pinfunction "NC_111_P1") (pintype "passive+no_connect"))
    )
    (net (code "143") (name "unconnected-(U201B-NC_112-PadP2)") (class "Default")
      (node (ref "U201") (pin "P2") (pinfunction "NC_112_P2") (pintype "passive+no_connect"))
    )
    (net (code "144") (name "unconnected-(U201B-NC_113-PadP7)") (class "Default")
      (node (ref "U201") (pin "P7") (pinfunction "NC_113_P7") (pintype "passive+no_connect"))
    )
    (net (code "145") (name "unconnected-(U201B-NC_114-PadP8)") (class "Default")
      (node (ref "U201") (pin "P8") (pinfunction "NC_114_P8") (pintype "passive+no_connect"))
    )
    (net (code "146") (name "unconnected-(U201B-NC_115-PadP9)") (class "Default")
      (node (ref "U201") (pin "P9") (pinfunction "NC_115_P9") (pintype "passive+no_connect"))
    )
    (net (code "147") (name "unconnected-(U201B-NC_116-PadP10)") (class "Default")
      (node (ref "U201") (pin "P10") (pinfunction "NC_116_P10") (pintype "passive+no_connect"))
    )
    (net (code "148") (name "unconnected-(U201B-NC_117-PadP11)") (class "Default")
      (node (ref "U201") (pin "P11") (pinfunction "NC_117_P11") (pintype "passive+no_connect"))
    )
    (net (code "149") (name "unconnected-(U201B-NC_118-PadP12)") (class "Default")
      (node (ref "U201") (pin "P12") (pinfunction "NC_118_P12") (pintype "passive+no_connect"))
    )
    (net (code "150") (name "unconnected-(U201B-NC_119-PadP13)") (class "Default")
      (node (ref "U201") (pin "P13") (pinfunction "NC_119_P13") (pintype "passive+no_connect"))
    )
    (net (code "151") (name "unconnected-(U201B-NC_120-PadP14)") (class "Default")
      (node (ref "U201") (pin "P14") (pinfunction "NC_120_P14") (pintype "passive+no_connect"))
    )
    (net (code "152") (name "unconnected-(U202-CT-Pad4)") (class "Default")
      (node (ref "U202") (pin "4") (pinfunction "CT_4") (pintype "passive+no_connect"))
    )
  )
)
